# Schematic.net
KiCad netlist of a schematic drawn in Altium Designer
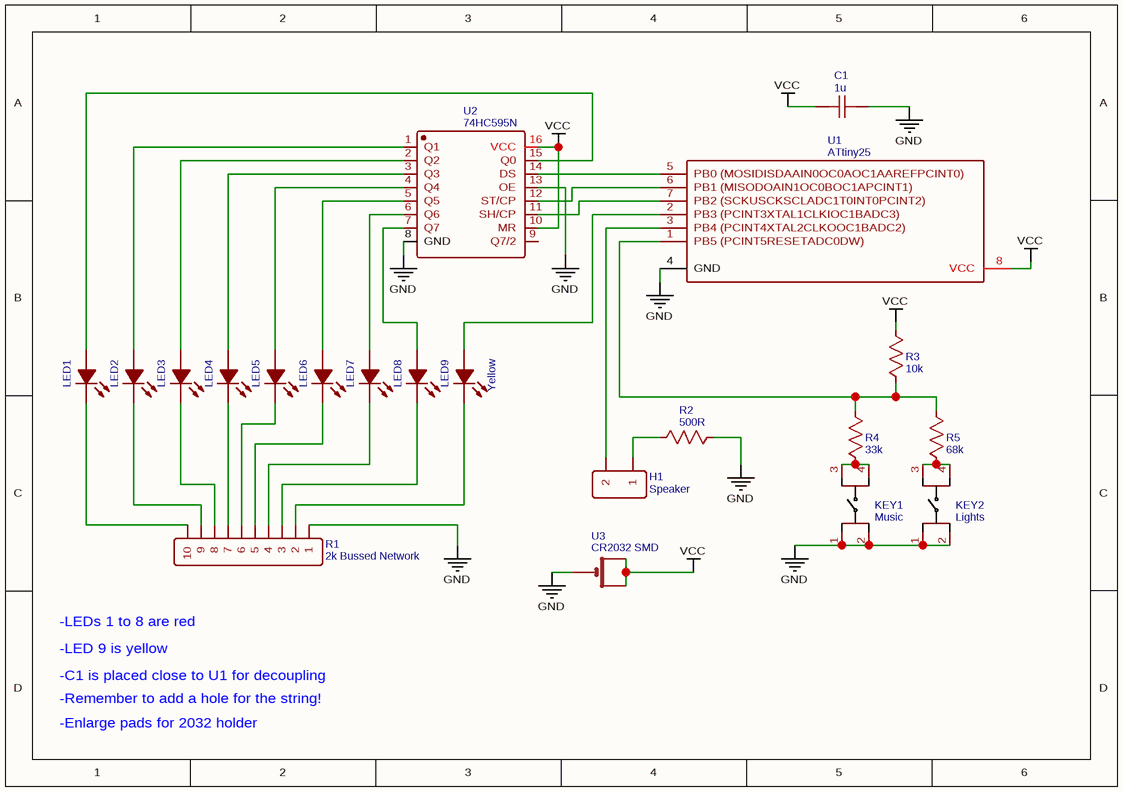
[diagram p0: Schematic.schdoc]

(export (version "E")
  (design (tool "Eeschema 10.0.6"))
  (components
    (comp (ref "C1") (value "1u") (libsource (lib "altium-import") (part "root_1_1u_")))
    (comp (ref "H1")
      (value "Speaker")
      (fields (field (name "BOM_MANUFACTURER PART") "826629-2") (field (name "BOM_SUPPLIER PART") "C86471"))
      (libsource (lib "altium-import") (part "root_3_Speaker_"))
    )
    (comp (ref "KEY1")
      (value "Music")
      (fields
        (field (name "BOM_MANUFACTURER PART") "TS-1102-5016")
        (field (name "BOM_SUPPLIER PART") "C111609")
        (field (name "CONTRIBUTOR") "EasyEDA")
      )
      (libsource (lib "altium-import") (part "root_1_Music_"))
    )
    (comp (ref "KEY2")
      (value "Lights")
      (fields
        (field (name "BOM_MANUFACTURER PART") "TS-1102-5016")
        (field (name "BOM_SUPPLIER PART") "C111609")
        (field (name "CONTRIBUTOR") "EasyEDA")
      )
      (libsource (lib "altium-import") (part "root_1_Lights_"))
    )
    (comp (ref "LED1")
      (value "204-10SURD/S530-A3")
      (fields (field (name "BOM_SUPPLIER PART") "C99772"))
      (libsource (lib "altium-import") (part "root_3_204-10SURD/S530-A3_"))
    )
    (comp (ref "LED2")
      (value "204-10SURD/S530-A3")
      (fields (field (name "BOM_SUPPLIER PART") "C99772"))
      (libsource (lib "altium-import") (part "root_3_204-10SURD/S530-A3_"))
    )
    (comp (ref "LED3")
      (value "204-10SURD/S530-A3")
      (fields (field (name "BOM_SUPPLIER PART") "C99772"))
      (libsource (lib "altium-import") (part "root_3_204-10SURD/S530-A3_"))
    )
    (comp (ref "LED4")
      (value "204-10SURD/S530-A3")
      (fields (field (name "BOM_SUPPLIER PART") "C99772"))
      (libsource (lib "altium-import") (part "root_3_204-10SURD/S530-A3_"))
    )
    (comp (ref "LED5")
      (value "204-10SURD/S530-A3")
      (fields (field (name "BOM_SUPPLIER PART") "C99772"))
      (libsource (lib "altium-import") (part "root_3_204-10SURD/S530-A3_"))
    )
    (comp (ref "LED6")
      (value "204-10SURD/S530-A3")
      (fields (field (name "BOM_SUPPLIER PART") "C99772"))
      (libsource (lib "altium-import") (part "root_3_204-10SURD/S530-A3_"))
    )
    (comp (ref "LED7")
      (value "204-10SURD/S530-A3")
      (fields (field (name "BOM_SUPPLIER PART") "C99772"))
      (libsource (lib "altium-import") (part "root_3_204-10SURD/S530-A3_"))
    )
    (comp (ref "LED8")
      (value "204-10SURD/S530-A3")
      (fields (field (name "BOM_SUPPLIER PART") "C99772"))
      (libsource (lib "altium-import") (part "root_3_204-10SURD/S530-A3_"))
    )
    (comp (ref "LED9")
      (value "Yellow")
      (fields
        (field (name "BOM_MANUFACTURER PART") "204-10SURD/S530-A3")
        (field (name "BOM_SUPPLIER PART") "C99772")
      )
      (libsource (lib "altium-import") (part "root_3_Yellow_"))
    )
    (comp (ref "R1")
      (value "2k Bussed Network")
      (fields
        (field (name "BOM_MANUFACTURER PART") "2.54mm 1*10P Straight Female header Gold-plated")
        (field (name "BOM_SUPPLIER PART") "C35445")
      )
      (libsource (lib "altium-import") (part "root_3_2k Bussed Network_"))
    )
    (comp (ref "R2") (value "500R") (libsource (lib "altium-import") (part "root_0_500R_")))
    (comp (ref "R3") (value "10k") (libsource (lib "altium-import") (part "root_1_10k_")))
    (comp (ref "R4") (value "33k") (libsource (lib "altium-import") (part "root_1_33k_")))
    (comp (ref "R5") (value "68k") (libsource (lib "altium-import") (part "root_1_68k_")))
    (comp (ref "U1") (value "ATtiny25") (libsource (lib "altium-import") (part "root_0_ATtiny25_")))
    (comp (ref "U2") (value "74HC595N") (libsource (lib "altium-import") (part "root_0_74HC595N_")))
    (comp (ref "U3")
      (value "CR2032 SMD")
      (fields (field (name "CONTRIBUTOR") "Adafruit"))
      (libsource (lib "altium-import") (part "root_0_CR2032 SMD_"))
    )
  )
  (nets
    (net (code "1") (name "GND") (class "Default")
      (node (ref "C1") (pin "1") (pinfunction "1_1") (pintype "passive"))
      (node (ref "KEY1") (pin "1") (pinfunction "1_1") (pintype "passive"))
      (node (ref "KEY1") (pin "2") (pinfunction "2_2") (pintype "passive"))
      (node (ref "KEY2") (pin "1") (pinfunction "1_1") (pintype "passive"))
      (node (ref "KEY2") (pin "2") (pinfunction "2_2") (pintype "passive"))
      (node (ref "R1") (pin "1") (pinfunction "1_1") (pintype "passive"))
      (node (ref "R2") (pin "2") (pinfunction "2_2") (pintype "passive"))
      (node (ref "U1") (pin "4") (pinfunction "GND_4") (pintype "passive"))
      (node (ref "U2") (pin "13") (pinfunction "OE_13") (pintype "passive"))
      (node (ref "U2") (pin "8") (pinfunction "GND_8") (pintype "passive"))
      (node (ref "U3") (pin "-") (pinfunction "-_-") (pintype "passive"))
    )
    (net (code "2") (name "Net-(H1-Pad1)") (class "Default")
      (node (ref "H1") (pin "1") (pinfunction "1_1") (pintype "passive"))
      (node (ref "R2") (pin "1") (pinfunction "1_1") (pintype "passive"))
    )
    (net (code "3") (name "Net-(KEY1-Pad3)") (class "Default")
      (node (ref "KEY1") (pin "3") (pinfunction "3_3") (pintype "passive"))
      (node (ref "KEY1") (pin "4") (pinfunction "4_4") (pintype "passive"))
      (node (ref "R4") (pin "1") (pinfunction "1_1") (pintype "passive"))
    )
    (net (code "4") (name "Net-(KEY2-Pad3)") (class "Default")
      (node (ref "KEY2") (pin "3") (pinfunction "3_3") (pintype "passive"))
      (node (ref "KEY2") (pin "4") (pinfunction "4_4") (pintype "passive"))
      (node (ref "R5") (pin "1") (pinfunction "1_1") (pintype "passive"))
    )
    (net (code "5") (name "Net-(LED1-A)") (class "Default")
      (node (ref "LED1") (pin "1") (pinfunction "A_1") (pintype "passive"))
      (node (ref "U2") (pin "15") (pinfunction "Q0_15") (pintype "passive"))
    )
    (net (code "6") (name "Net-(LED1-K)") (class "Default")
      (node (ref "LED1") (pin "2") (pinfunction "K_2") (pintype "passive"))
      (node (ref "R1") (pin "10") (pinfunction "10_10") (pintype "passive"))
    )
    (net (code "7") (name "Net-(LED2-A)") (class "Default")
      (node (ref "LED2") (pin "1") (pinfunction "A_1") (pintype "passive"))
      (node (ref "U2") (pin "1") (pinfunction "Q1_1") (pintype "passive"))
    )
    (net (code "8") (name "Net-(LED2-K)") (class "Default")
      (node (ref "LED2") (pin "2") (pinfunction "K_2") (pintype "passive"))
      (node (ref "R1") (pin "9") (pinfunction "9_9") (pintype "passive"))
    )
    (net (code "9") (name "Net-(LED3-A)") (class "Default")
      (node (ref "LED3") (pin "1") (pinfunction "A_1") (pintype "passive"))
      (node (ref "U2") (pin "2") (pinfunction "Q2_2") (pintype "passive"))
    )
    (net (code "10") (name "Net-(LED3-K)") (class "Default")
      (node (ref "LED3") (pin "2") (pinfunction "K_2") (pintype "passive"))
      (node (ref "R1") (pin "8") (pinfunction "8_8") (pintype "passive"))
    )
    (net (code "11") (name "Net-(LED4-A)") (class "Default")
      (node (ref "LED4") (pin "1") (pinfunction "A_1") (pintype "passive"))
      (node (ref "U2") (pin "3") (pinfunction "Q3_3") (pintype "passive"))
    )
    (net (code "12") (name "Net-(LED4-K)") (class "Default")
      (node (ref "LED4") (pin "2") (pinfunction "K_2") (pintype "passive"))
      (node (ref "R1") (pin "7") (pinfunction "7_7") (pintype "passive"))
    )
    (net (code "13") (name "Net-(LED5-A)") (class "Default")
      (node (ref "LED5") (pin "1") (pinfunction "A_1") (pintype "passive"))
      (node (ref "U2") (pin "4") (pinfunction "Q4_4") (pintype "passive"))
    )
    (net (code "14") (name "Net-(LED5-K)") (class "Default")
      (node (ref "LED5") (pin "2") (pinfunction "K_2") (pintype "passive"))
      (node (ref "R1") (pin "6") (pinfunction "6_6") (pintype "passive"))
    )
    (net (code "15") (name "Net-(LED6-A)") (class "Default")
      (node (ref "LED6") (pin "1") (pinfunction "A_1") (pintype "passive"))
      (node (ref "U2") (pin "5") (pinfunction "Q5_5") (pintype "passive"))
    )
    (net (code "16") (name "Net-(LED6-K)") (class "Default")
      (node (ref "LED6") (pin "2") (pinfunction "K_2") (pintype "passive"))
      (node (ref "R1") (pin "5") (pinfunction "5_5") (pintype "passive"))
    )
    (net (code "17") (name "Net-(LED7-A)") (class "Default")
      (node (ref "LED7") (pin "1") (pinfunction "A_1") (pintype "passive"))
      (node (ref "U2") (pin "6") (pinfunction "Q6_6") (pintype "passive"))
    )
    (net (code "18") (name "Net-(LED7-K)") (class "Default")
      (node (ref "LED7") (pin "2") (pinfunction "K_2") (pintype "passive"))
      (node (ref "R1") (pin "4") (pinfunction "4_4") (pintype "passive"))
    )
    (net (code "19") (name "Net-(LED8-A)") (class "Default")
      (node (ref "LED8") (pin "1") (pinfunction "A_1") (pintype "passive"))
      (node (ref "U2") (pin "7") (pinfunction "Q7_7") (pintype "passive"))
    )
    (net (code "20") (name "Net-(LED8-K)") (class "Default")
      (node (ref "LED8") (pin "2") (pinfunction "K_2") (pintype "passive"))
      (node (ref "R1") (pin "3") (pinfunction "3_3") (pintype "passive"))
    )
    (net (code "21") (name "Net-(LED9-A)") (class "Default")
      (node (ref "LED9") (pin "1") (pinfunction "A_1") (pintype "passive"))
      (node (ref "U1") (pin "2") (pinfunction "PB3_(PCINT3XTAL1CLKIOC1BADC3)_2") (pintype "passive"))
    )
    (net (code "22") (name "Net-(LED9-K)") (class "Default")
      (node (ref "LED9") (pin "2") (pinfunction "K_2") (pintype "passive"))
      (node (ref "R1") (pin "2") (pinfunction "2_2") (pintype "passive"))
    )
    (net (code "23") (name "Net-(U1-PB0_(MOSIDISDAAIN0OC0AOC1AAREFPCINT0))") (class "Default")
      (node (ref "U1") (pin "5") (pinfunction "PB0_(MOSIDISDAAIN0OC0AOC1AAREFPCINT0)_5") (pintype "passive"))
      (node (ref "U2") (pin "14") (pinfunction "DS_14") (pintype "passive"))
    )
    (net (code "24") (name "Net-(U1-PB1_(MISODOAIN1OC0BOC1APCINT1))") (class "Default")
      (node (ref "U1") (pin "6") (pinfunction "PB1_(MISODOAIN1OC0BOC1APCINT1)_6") (pintype "passive"))
      (node (ref "U2") (pin "12") (pinfunction "ST/CP_12") (pintype "passive"))
    )
    (net (code "25") (name "Net-(U1-PB2_(SCKUSCKSCLADC1T0INT0PCINT2))") (class "Default")
      (node (ref "U1") (pin "7") (pinfunction "PB2_(SCKUSCKSCLADC1T0INT0PCINT2)_7") (pintype "passive"))
      (node (ref "U2") (pin "11") (pinfunction "SH/CP_11") (pintype "passive"))
    )
    (net (code "26") (name "Net-(U1-PB4_(PCINT4XTAL2CLKOOC1BADC2))") (class "Default")
      (node (ref "H1") (pin "2") (pinfunction "2_2") (pintype "passive"))
      (node (ref "U1") (pin "3") (pinfunction "PB4_(PCINT4XTAL2CLKOOC1BADC2)_3") (pintype "passive"))
    )
    (net (code "27") (name "Net-(U1-PB5_(PCINT5RESETADC0DW))") (class "Default")
      (node (ref "R3") (pin "1") (pinfunction "1_1") (pintype "passive"))
      (node (ref "R4") (pin "2") (pinfunction "2_2") (pintype "passive"))
      (node (ref "R5") (pin "2") (pinfunction "2_2") (pintype "passive"))
      (node (ref "U1") (pin "1") (pinfunction "PB5_(PCINT5RESETADC0DW)_1") (pintype "passive"))
    )
    (net (code "28") (name "VCC") (class "Default")
      (node (ref "C1") (pin "2") (pinfunction "2_2") (pintype "passive"))
      (node (ref "R3") (pin "2") (pinfunction "2_2") (pintype "passive"))
      (node (ref "U1") (pin "8") (pinfunction "VCC_8") (pintype "passive"))
      (node (ref "U2") (pin "10") (pinfunction "MR_10") (pintype "passive"))
      (node (ref "U2") (pin "16") (pinfunction "VCC_16") (pintype "passive"))
      (node (ref "U3") (pin "+1") (pinfunction "+_+1") (pintype "passive"))
      (node (ref "U3") (pin "+2") (pinfunction "+1_+2") (pintype "passive"))
    )
    (net (code "29") (name "unconnected-(U2-Q7{slash}2-Pad9)") (class "Default")
      (node (ref "U2") (pin "9") (pinfunction "Q7/2_9") (pintype "passive"))
    )
  )
)
